# FABLAB_BADGE_00.net
KiCad netlist of a schematic drawn in Altium Designer
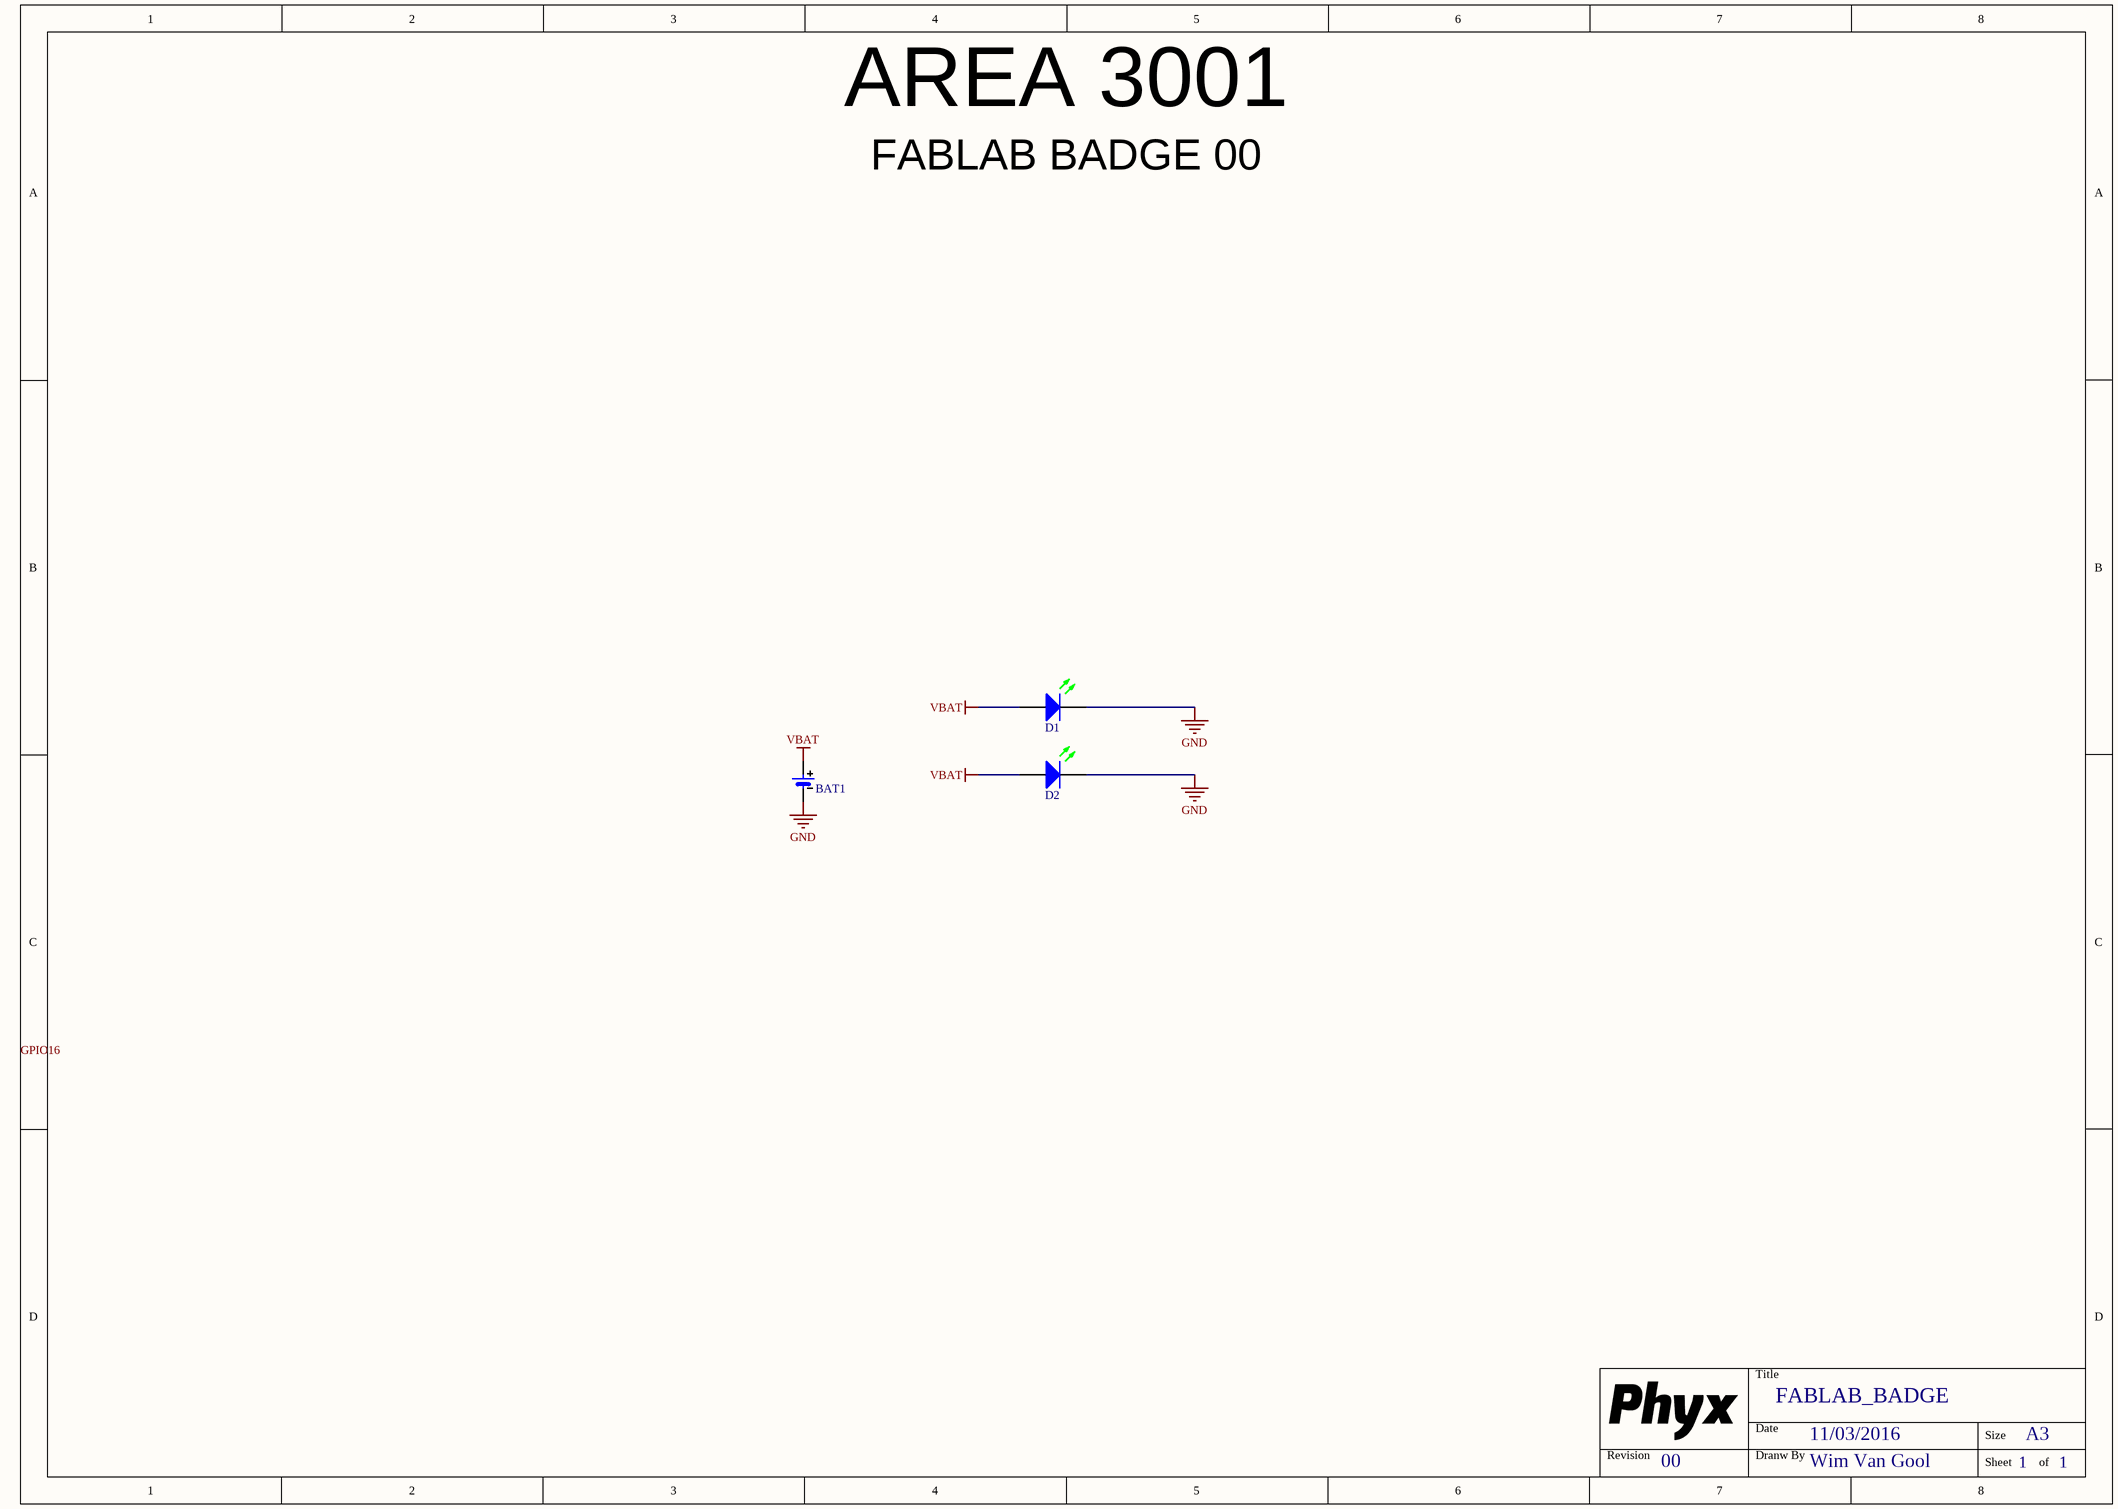
[diagram p0: FABLAB_BADGE_00.SchDoc]

(export (version "E")
  (design (tool "Eeschema 10.0.6"))
  (components
    (comp (ref "BAT1")
      (value "CR2032 Battery Holder")
      (footprint "BAT_CR2032_China")
      (description "BAT 20mm Coin Cell Holder Genericf")
      (libsource (lib "Phyx_Components") (part "BAT_2"))
    )
    (comp (ref "D1")
      (value "Default 5mm Green LED")
      (footprint "LED_5MM_GR")
      (description "=Description")
      (libsource (lib "Phyx_Components") (part "LED_GREEN"))
    )
    (comp (ref "D2")
      (value "Default 5mm Green LED")
      (footprint "LED_5MM_GR")
      (description "=Description")
      (libsource (lib "Phyx_Components") (part "LED_GREEN"))
    )
  )
  (nets
    (net (code "2") (name "GND") (class "Default")
      (node (ref "BAT1") (pin "2") (pinfunction "2_2") (pintype "passive"))
      (node (ref "D1") (pin "2") (pinfunction "K_2") (pintype "passive"))
      (node (ref "D2") (pin "2") (pinfunction "K_2") (pintype "passive"))
    )
    (net (code "3") (name "VBAT") (class "Default")
      (node (ref "BAT1") (pin "1") (pinfunction "1_1") (pintype "passive"))
      (node (ref "D1") (pin "1") (pinfunction "A_1") (pintype "passive"))
      (node (ref "D2") (pin "1") (pinfunction "A_1") (pintype "passive"))
    )
  )
)
